# EH_400_Mini-Synth.net
KiCad netlist of a schematic drawn in EAGLE
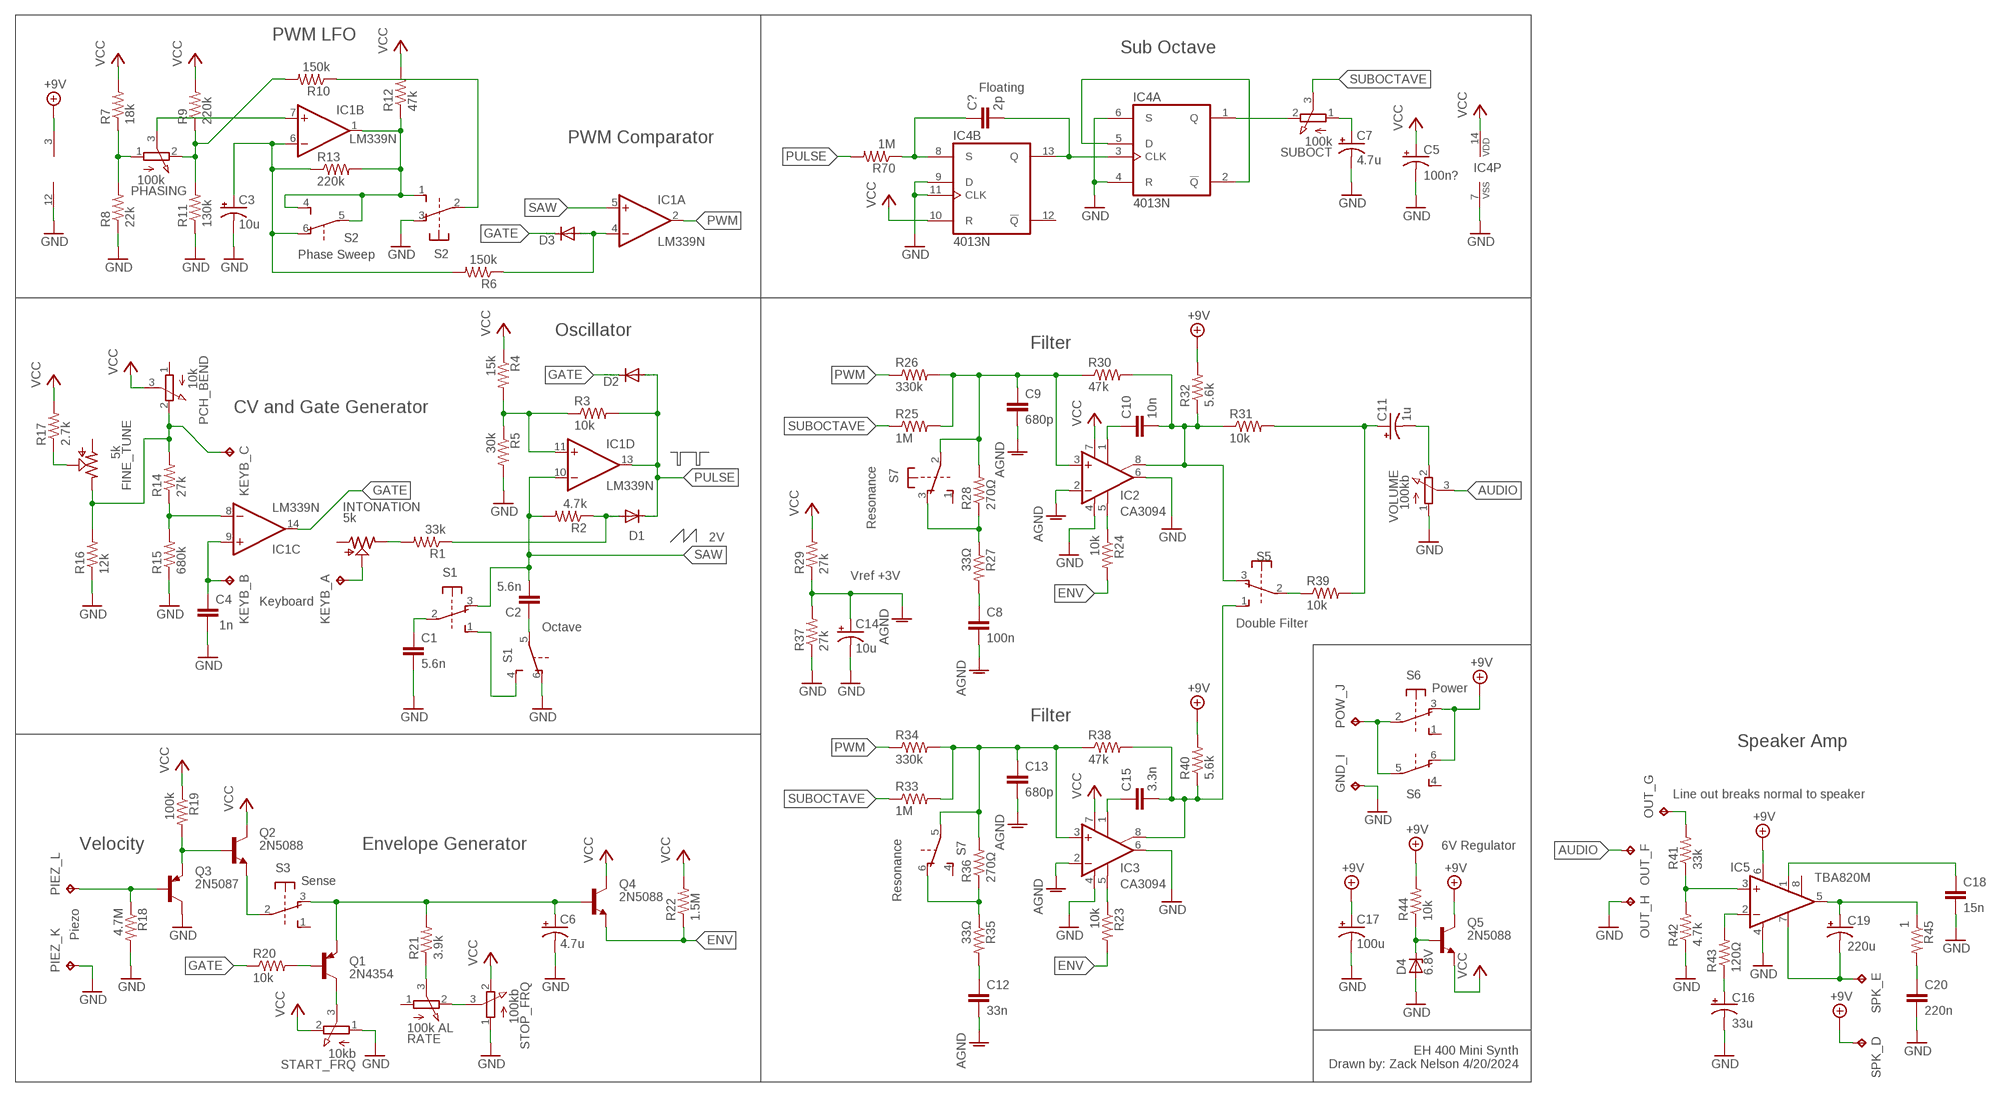
[diagram p0: schematic, sheet 1]

(export (version "E")
  (design (tool "Eeschema 10.0.6"))
  (components
    (comp (ref "C1")
      (value "5.6n")
      (footprint "eagle-import:C050-024X044")
      (libsource (lib "eagle-import") (part "C-EU050-024X044"))
    )
    (comp (ref "C2")
      (value "5.6n")
      (footprint "eagle-import:C050-024X044")
      (libsource (lib "eagle-import") (part "C-EU050-024X044"))
    )
    (comp (ref "C3")
      (value "10u")
      (footprint "eagle-import:E3,5-8")
      (libsource (lib "eagle-import") (part "CPOL-USE3.5-8"))
    )
    (comp (ref "C4")
      (value "1n")
      (footprint "eagle-import:C050-024X044")
      (libsource (lib "eagle-import") (part "C-EU050-024X044"))
    )
    (comp (ref "C5")
      (value "100n?")
      (footprint "eagle-import:E3,5-8")
      (libsource (lib "eagle-import") (part "CPOL-USE3.5-8"))
    )
    (comp (ref "C6")
      (value "4.7u")
      (footprint "eagle-import:E3,5-8")
      (libsource (lib "eagle-import") (part "CPOL-USE3.5-8"))
    )
    (comp (ref "C7")
      (value "4.7u")
      (footprint "eagle-import:E5-4")
      (libsource (lib "eagle-import") (part "CPOL-USE5-4"))
    )
    (comp (ref "C8")
      (value "100n")
      (footprint "eagle-import:C050-024X044")
      (libsource (lib "eagle-import") (part "C-EU050-024X044"))
    )
    (comp (ref "C9")
      (value "680p")
      (footprint "eagle-import:C050-024X044")
      (libsource (lib "eagle-import") (part "C-EU050-024X044"))
    )
    (comp (ref "C10")
      (value "10n")
      (footprint "eagle-import:C050-025X075")
      (libsource (lib "eagle-import") (part "C-EU050-025X075"))
    )
    (comp (ref "C11")
      (value "1u")
      (footprint "eagle-import:E5-4")
      (libsource (lib "eagle-import") (part "CPOL-USE5-4"))
    )
    (comp (ref "C12")
      (value "33n")
      (footprint "eagle-import:C050-024X044")
      (libsource (lib "eagle-import") (part "C-EU050-024X044"))
    )
    (comp (ref "C13")
      (value "680p")
      (footprint "eagle-import:C050-024X044")
      (libsource (lib "eagle-import") (part "C-EU050-024X044"))
    )
    (comp (ref "C14")
      (value "10u")
      (footprint "eagle-import:E3,5-8")
      (libsource (lib "eagle-import") (part "CPOL-USE3.5-8"))
    )
    (comp (ref "C15")
      (value "3.3n")
      (footprint "eagle-import:C050-024X044")
      (libsource (lib "eagle-import") (part "C-EU050-024X044"))
    )
    (comp (ref "C16")
      (value "33u")
      (footprint "eagle-import:E3,5-8")
      (libsource (lib "eagle-import") (part "CPOL-USE3.5-8"))
    )
    (comp (ref "C17")
      (value "100u")
      (footprint "eagle-import:TT5D9")
      (libsource (lib "eagle-import") (part "CPOL-USTT5D9"))
    )
    (comp (ref "C18")
      (value "15n")
      (footprint "eagle-import:C050-024X044")
      (libsource (lib "eagle-import") (part "C-EU050-024X044"))
    )
    (comp (ref "C19")
      (value "220u")
      (footprint "eagle-import:TT5D9")
      (libsource (lib "eagle-import") (part "CPOL-USTT5D9"))
    )
    (comp (ref "C20")
      (value "220n")
      (footprint "eagle-import:C050-024X044")
      (libsource (lib "eagle-import") (part "C-EU050-024X044"))
    )
    (comp (ref "C?")
      (value "2p")
      (footprint "eagle-import:C075-032X103")
      (libsource (lib "eagle-import") (part "C-EU075-032X103"))
    )
    (comp (ref "D1")
      (value "DIODE-DO07")
      (footprint "eagle-import:DO07")
      (libsource (lib "eagle-import") (part "DIODE-DO07"))
    )
    (comp (ref "D2")
      (value "DIODE-DO07")
      (footprint "eagle-import:DO07")
      (libsource (lib "eagle-import") (part "DIODE-DO07"))
    )
    (comp (ref "D3")
      (value "DIODE-DO07")
      (footprint "eagle-import:DO07")
      (libsource (lib "eagle-import") (part "DIODE-DO07"))
    )
    (comp (ref "D4")
      (value "6.8V")
      (footprint "eagle-import:ZDIO-7.5")
      (libsource (lib "eagle-import") (part "ZENER-DIODEZD-7.5"))
    )
    (comp (ref "FINE_TUNE")
      (value "5k")
      (footprint "eagle-import:ECP10S")
      (libsource (lib "eagle-import") (part "TRIM_US-ECP10S"))
    )
    (comp (ref "GND_I")
      (value "TPB1,27")
      (footprint "eagle-import:B1,27")
      (libsource (lib "eagle-import") (part "TPB1,27"))
    )
    (comp (ref "IC1")
      (value "LM339N")
      (footprint "eagle-import:DIL14")
      (libsource (lib "eagle-import") (part "LM339N"))
    )
    (comp (ref "IC2")
      (value "CA3094")
      (footprint "eagle-import:DIL08")
      (libsource (lib "eagle-import") (part "3080NLM"))
    )
    (comp (ref "IC3")
      (value "CA3094")
      (footprint "eagle-import:DIL08")
      (libsource (lib "eagle-import") (part "3080NLM"))
    )
    (comp (ref "IC4")
      (value "4013N")
      (footprint "eagle-import:DIL14")
      (libsource (lib "eagle-import") (part "4013N"))
    )
    (comp (ref "IC5")
      (value "TBA820M")
      (footprint "eagle-import:DIL08")
      (libsource (lib "eagle-import") (part "LM386?-N1"))
    )
    (comp (ref "INTONATION")
      (value "5k")
      (footprint "eagle-import:ECP10S")
      (libsource (lib "eagle-import") (part "TRIM_US-ECP10S"))
    )
    (comp (ref "KEYB_A")
      (value "TPB1,27")
      (footprint "eagle-import:B1,27")
      (libsource (lib "eagle-import") (part "TPB1,27"))
    )
    (comp (ref "KEYB_B")
      (value "TPB1,27")
      (footprint "eagle-import:B1,27")
      (libsource (lib "eagle-import") (part "TPB1,27"))
    )
    (comp (ref "KEYB_C")
      (value "TPB1,27")
      (footprint "eagle-import:B1,27")
      (libsource (lib "eagle-import") (part "TPB1,27"))
    )
    (comp (ref "OUT_F")
      (value "TPB1,27")
      (footprint "eagle-import:B1,27")
      (libsource (lib "eagle-import") (part "TPB1,27"))
    )
    (comp (ref "OUT_G")
      (value "TPB1,27")
      (footprint "eagle-import:B1,27")
      (libsource (lib "eagle-import") (part "TPB1,27"))
    )
    (comp (ref "OUT_H")
      (value "TPB1,27")
      (footprint "eagle-import:B1,27")
      (libsource (lib "eagle-import") (part "TPB1,27"))
    )
    (comp (ref "PCH_BEND")
      (value "10k")
      (footprint "eagle-import:FADER-EHX")
      (libsource (lib "eagle-import") (part "EVUF"))
    )
    (comp (ref "PHASING")
      (value "100k")
      (footprint "eagle-import:FADER-EHX")
      (libsource (lib "eagle-import") (part "EVUF"))
    )
    (comp (ref "PIEZ_K")
      (value "TPB1,27")
      (footprint "eagle-import:B1,27")
      (libsource (lib "eagle-import") (part "TPB1,27"))
    )
    (comp (ref "PIEZ_L")
      (value "TPB1,27")
      (footprint "eagle-import:B1,27")
      (libsource (lib "eagle-import") (part "TPB1,27"))
    )
    (comp (ref "POW_J")
      (value "TPB1,27")
      (footprint "eagle-import:B1,27")
      (libsource (lib "eagle-import") (part "TPB1,27"))
    )
    (comp (ref "Q1")
      (value "2N4354")
      (footprint "eagle-import:TO92-EBC")
      (libsource (lib "eagle-import") (part "-PNP-TO92-EBC2N5087"))
    )
    (comp (ref "Q2")
      (value "2N5088")
      (footprint "eagle-import:TO92-EBC")
      (libsource (lib "eagle-import") (part "-NPN-TO92-EBC2N5088"))
    )
    (comp (ref "Q3")
      (value "2N5087")
      (footprint "eagle-import:TO92-EBC")
      (libsource (lib "eagle-import") (part "-PNP-TO92-EBC2N5087"))
    )
    (comp (ref "Q4")
      (value "2N5088")
      (footprint "eagle-import:TO92-EBC")
      (libsource (lib "eagle-import") (part "-NPN-TO92-EBC2N5088"))
    )
    (comp (ref "Q5")
      (value "2N5088")
      (footprint "eagle-import:TO92-EBC")
      (libsource (lib "eagle-import") (part "-NPN-TO92-EBC2N5088"))
    )
    (comp (ref "R1")
      (value "33k")
      (footprint "eagle-import:0207_12")
      (libsource (lib "eagle-import") (part "R-US_0207/12"))
    )
    (comp (ref "R2")
      (value "4.7k")
      (footprint "eagle-import:0207_12")
      (libsource (lib "eagle-import") (part "R-US_0207/12"))
    )
    (comp (ref "R3")
      (value "10k")
      (footprint "eagle-import:0207_12")
      (libsource (lib "eagle-import") (part "R-US_0207/12"))
    )
    (comp (ref "R4")
      (value "15k")
      (footprint "eagle-import:0207_12")
      (libsource (lib "eagle-import") (part "R-US_0207/12"))
    )
    (comp (ref "R5")
      (value "30k")
      (footprint "eagle-import:0207_12")
      (libsource (lib "eagle-import") (part "R-US_0207/12"))
    )
    (comp (ref "R6")
      (value "150k")
      (footprint "eagle-import:0207_12")
      (libsource (lib "eagle-import") (part "R-US_0207/12"))
    )
    (comp (ref "R7")
      (value "18k")
      (footprint "eagle-import:0207_12")
      (libsource (lib "eagle-import") (part "R-US_0207/12"))
    )
    (comp (ref "R8")
      (value "22k")
      (footprint "eagle-import:0207_12")
      (libsource (lib "eagle-import") (part "R-US_0207/12"))
    )
    (comp (ref "R9")
      (value "220k")
      (footprint "eagle-import:0207_12")
      (libsource (lib "eagle-import") (part "R-US_0207/12"))
    )
    (comp (ref "R10")
      (value "150k")
      (footprint "eagle-import:0207_12")
      (libsource (lib "eagle-import") (part "R-US_0207/12"))
    )
    (comp (ref "R11")
      (value "130k")
      (footprint "eagle-import:0207_12")
      (libsource (lib "eagle-import") (part "R-US_0207/12"))
    )
    (comp (ref "R12")
      (value "47k")
      (footprint "eagle-import:0207_12")
      (libsource (lib "eagle-import") (part "R-US_0207/12"))
    )
    (comp (ref "R13")
      (value "220k")
      (footprint "eagle-import:0207_12")
      (libsource (lib "eagle-import") (part "R-US_0207/12"))
    )
    (comp (ref "R14")
      (value "27k")
      (footprint "eagle-import:0207_12")
      (libsource (lib "eagle-import") (part "R-US_0207/12"))
    )
    (comp (ref "R15")
      (value "680k")
      (footprint "eagle-import:0207_12")
      (libsource (lib "eagle-import") (part "R-US_0207/12"))
    )
    (comp (ref "R16")
      (value "12k")
      (footprint "eagle-import:0207_12")
      (libsource (lib "eagle-import") (part "R-US_0207/12"))
    )
    (comp (ref "R17")
      (value "2.7k")
      (footprint "eagle-import:0207_12")
      (libsource (lib "eagle-import") (part "R-US_0207/12"))
    )
    (comp (ref "R18")
      (value "4.7M")
      (footprint "eagle-import:0207_12")
      (libsource (lib "eagle-import") (part "R-US_0207/12"))
    )
    (comp (ref "R19")
      (value "100k")
      (footprint "eagle-import:0207_12")
      (libsource (lib "eagle-import") (part "R-US_0207/12"))
    )
    (comp (ref "R20")
      (value "10k")
      (footprint "eagle-import:0207_12")
      (libsource (lib "eagle-import") (part "R-US_0207/12"))
    )
    (comp (ref "R21")
      (value "3.9k")
      (footprint "eagle-import:0207_12")
      (libsource (lib "eagle-import") (part "R-US_0207/12"))
    )
    (comp (ref "R22")
      (value "1.5M")
      (footprint "eagle-import:0207_12")
      (libsource (lib "eagle-import") (part "R-US_0207/12"))
    )
    (comp (ref "R23")
      (value "10k")
      (footprint "eagle-import:0207_12")
      (libsource (lib "eagle-import") (part "R-US_0207/12"))
    )
    (comp (ref "R24")
      (value "10k")
      (footprint "eagle-import:0207_12")
      (libsource (lib "eagle-import") (part "R-US_0207/12"))
    )
    (comp (ref "R25")
      (value "1M")
      (footprint "eagle-import:0207_12")
      (libsource (lib "eagle-import") (part "R-US_0207/12"))
    )
    (comp (ref "R26")
      (value "330k")
      (footprint "eagle-import:0207_12")
      (libsource (lib "eagle-import") (part "R-US_0207/12"))
    )
    (comp (ref "R27")
      (value "33Ω")
      (footprint "eagle-import:0207_12")
      (libsource (lib "eagle-import") (part "R-US_0207/12"))
    )
    (comp (ref "R28")
      (value "270Ω")
      (footprint "eagle-import:0207_12")
      (libsource (lib "eagle-import") (part "R-US_0207/12"))
    )
    (comp (ref "R29")
      (value "27k")
      (footprint "eagle-import:0207_12")
      (libsource (lib "eagle-import") (part "R-US_0207/12"))
    )
    (comp (ref "R30")
      (value "47k")
      (footprint "eagle-import:0207_12")
      (libsource (lib "eagle-import") (part "R-US_0207/12"))
    )
    (comp (ref "R31")
      (value "10k")
      (footprint "eagle-import:0207_12")
      (libsource (lib "eagle-import") (part "R-US_0207/12"))
    )
    (comp (ref "R32")
      (value "5.6k")
      (footprint "eagle-import:0207_12")
      (libsource (lib "eagle-import") (part "R-US_0207/12"))
    )
    (comp (ref "R33")
      (value "1M")
      (footprint "eagle-import:0207_12")
      (libsource (lib "eagle-import") (part "R-US_0207/12"))
    )
    (comp (ref "R34")
      (value "330k")
      (footprint "eagle-import:0207_12")
      (libsource (lib "eagle-import") (part "R-US_0207/12"))
    )
    (comp (ref "R35")
      (value "33Ω")
      (footprint "eagle-import:0207_12")
      (libsource (lib "eagle-import") (part "R-US_0207/12"))
    )
    (comp (ref "R36")
      (value "270Ω")
      (footprint "eagle-import:0207_12")
      (libsource (lib "eagle-import") (part "R-US_0207/12"))
    )
    (comp (ref "R37")
      (value "27k")
      (footprint "eagle-import:0207_12")
      (libsource (lib "eagle-import") (part "R-US_0207/12"))
    )
    (comp (ref "R38")
      (value "47k")
      (footprint "eagle-import:0207_12")
      (libsource (lib "eagle-import") (part "R-US_0207/12"))
    )
    (comp (ref "R39")
      (value "10k")
      (footprint "eagle-import:0207_12")
      (libsource (lib "eagle-import") (part "R-US_0207/12"))
    )
    (comp (ref "R40")
      (value "5.6k")
      (footprint "eagle-import:0207_12")
      (libsource (lib "eagle-import") (part "R-US_0207/12"))
    )
    (comp (ref "R41")
      (value "33k")
      (footprint "eagle-import:0207_12")
      (libsource (lib "eagle-import") (part "R-US_0207/12"))
    )
    (comp (ref "R42")
      (value "4.7k")
      (footprint "eagle-import:0207_12")
      (libsource (lib "eagle-import") (part "R-US_0207/12"))
    )
    (comp (ref "R43")
      (value "120Ω")
      (footprint "eagle-import:0207_12")
      (libsource (lib "eagle-import") (part "R-US_0207/12"))
    )
    (comp (ref "R44")
      (value "10k")
      (footprint "eagle-import:0207_12")
      (libsource (lib "eagle-import") (part "R-US_0207/12"))
    )
    (comp (ref "R45")
      (value "1")
      (footprint "eagle-import:0207_12")
      (libsource (lib "eagle-import") (part "R-US_0207/12"))
    )
    (comp (ref "R70")
      (value "1M")
      (footprint "eagle-import:0207_12")
      (libsource (lib "eagle-import") (part "R-US_0207/12"))
    )
    (comp (ref "RATE")
      (value "100k AL")
      (footprint "eagle-import:FADER-EHX")
      (libsource (lib "eagle-import") (part "EVUF"))
    )
    (comp (ref "S1")
      (value "Octave")
      (footprint "eagle-import:SLIDE")
      (libsource (lib "eagle-import") (part "9077-2S"))
    )
    (comp (ref "S2")
      (value "Phase")
      (footprint "eagle-import:SLIDE")
      (libsource (lib "eagle-import") (part "9077-2S"))
    )
    (comp (ref "S3")
      (value "Sense")
      (footprint "eagle-import:SLIDE")
      (libsource (lib "eagle-import") (part "9077-2S"))
    )
    (comp (ref "S5")
      (value "Double Filter")
      (footprint "eagle-import:SLIDE")
      (libsource (lib "eagle-import") (part "9077-2S"))
    )
    (comp (ref "S6")
      (value "Power")
      (footprint "eagle-import:SLIDE")
      (libsource (lib "eagle-import") (part "9077-2S"))
    )
    (comp (ref "S7")
      (value "9077-2S")
      (footprint "eagle-import:SLIDE")
      (libsource (lib "eagle-import") (part "9077-2S"))
    )
    (comp (ref "SPK_D")
      (value "TPB1,27")
      (footprint "eagle-import:B1,27")
      (libsource (lib "eagle-import") (part "TPB1,27"))
    )
    (comp (ref "SPK_E")
      (value "TPB1,27")
      (footprint "eagle-import:B1,27")
      (libsource (lib "eagle-import") (part "TPB1,27"))
    )
    (comp (ref "START_FRQ")
      (value "10kb")
      (footprint "eagle-import:FADER-EHX")
      (libsource (lib "eagle-import") (part "EVUF"))
    )
    (comp (ref "STOP_FRQ")
      (value "100kb")
      (footprint "eagle-import:FADER-EHX")
      (libsource (lib "eagle-import") (part "EVUF"))
    )
    (comp (ref "SUBOCT")
      (value "100k")
      (footprint "eagle-import:FADER-EHX")
      (libsource (lib "eagle-import") (part "EVUF"))
    )
    (comp (ref "VOLUME")
      (value "100kb")
      (footprint "eagle-import:FADER-EHX")
      (libsource (lib "eagle-import") (part "EVUF"))
    )
  )
  (nets
    (net (code "1") (name "+9V") (class "Default")
      (node (ref "C17") (pin "+") (pinfunction "+_+") (pintype "passive"))
      (node (ref "IC1") (pin "3") (pinfunction "V+_3") (pintype "power_in"))
      (node (ref "IC5") (pin "6") (pinfunction "VS_6") (pintype "power_in"))
      (node (ref "Q5") (pin "C") (pinfunction "C_C") (pintype "passive"))
      (node (ref "R32") (pin "2") (pinfunction "2_2") (pintype "passive"))
      (node (ref "R40") (pin "2") (pinfunction "2_2") (pintype "passive"))
      (node (ref "R44") (pin "2") (pinfunction "2_2") (pintype "passive"))
      (node (ref "S6") (pin "3") (pinfunction "O_3") (pintype "passive"))
      (node (ref "S6") (pin "6") (pinfunction "O_6") (pintype "passive"))
      (node (ref "SPK_D") (pin "TP") (pinfunction "TP_TP") (pintype "input"))
    )
    (net (code "2") (name "AGND") (class "Default")
      (node (ref "C12") (pin "2") (pinfunction "2_2") (pintype "passive"))
      (node (ref "C13") (pin "2") (pinfunction "2_2") (pintype "passive"))
      (node (ref "C14") (pin "+") (pinfunction "+_+") (pintype "passive"))
      (node (ref "C8") (pin "2") (pinfunction "2_2") (pintype "passive"))
      (node (ref "C9") (pin "2") (pinfunction "2_2") (pintype "passive"))
      (node (ref "IC2") (pin "2") (pinfunction "-IN_2") (pintype "input"))
      (node (ref "IC3") (pin "2") (pinfunction "-IN_2") (pintype "input"))
      (node (ref "R29") (pin "1") (pinfunction "1_1") (pintype "passive"))
      (node (ref "R37") (pin "2") (pinfunction "2_2") (pintype "passive"))
    )
    (net (code "3") (name "AUDIO") (class "Default")
      (node (ref "OUT_F") (pin "TP") (pinfunction "TP_TP") (pintype "input"))
      (node (ref "VOLUME") (pin "3") (pinfunction "S_3") (pintype "passive"))
    )
    (net (code "4") (name "ENV") (class "Default")
      (node (ref "Q4") (pin "E") (pinfunction "E_E") (pintype "passive"))
      (node (ref "R22") (pin "1") (pinfunction "1_1") (pintype "passive"))
      (node (ref "R23") (pin "2") (pinfunction "2_2") (pintype "passive"))
      (node (ref "R24") (pin "2") (pinfunction "2_2") (pintype "passive"))
    )
    (net (code "5") (name "GATE") (class "Default")
      (node (ref "D2") (pin "C") (pinfunction "C_C") (pintype "passive"))
      (node (ref "D3") (pin "C") (pinfunction "C_C") (pintype "passive"))
      (node (ref "IC1") (pin "14") (pinfunction "OUT_14") (pintype "open_collector"))
      (node (ref "R20") (pin "1") (pinfunction "1_1") (pintype "passive"))
    )
    (net (code "6") (name "GND") (class "Default")
      (node (ref "C1") (pin "2") (pinfunction "2_2") (pintype "passive"))
      (node (ref "C14") (pin "-") (pinfunction "-_-") (pintype "passive"))
      (node (ref "C16") (pin "-") (pinfunction "-_-") (pintype "passive"))
      (node (ref "C17") (pin "-") (pinfunction "-_-") (pintype "passive"))
      (node (ref "C18") (pin "2") (pinfunction "2_2") (pintype "passive"))
      (node (ref "C20") (pin "2") (pinfunction "2_2") (pintype "passive"))
      (node (ref "C3") (pin "-") (pinfunction "-_-") (pintype "passive"))
      (node (ref "C4") (pin "2") (pinfunction "2_2") (pintype "passive"))
      (node (ref "C5") (pin "-") (pinfunction "-_-") (pintype "passive"))
      (node (ref "C6") (pin "-") (pinfunction "-_-") (pintype "passive"))
      (node (ref "C7") (pin "-") (pinfunction "-_-") (pintype "passive"))
      (node (ref "D4") (pin "A") (pinfunction "A_A") (pintype "passive"))
      (node (ref "GND_I") (pin "TP") (pinfunction "TP_TP") (pintype "input"))
      (node (ref "IC1") (pin "12") (pinfunction "GND_12") (pintype "power_in"))
      (node (ref "IC2") (pin "4") (pinfunction "V-_4") (pintype "power_in"))
      (node (ref "IC2") (pin "6") (pinfunction "OUT_6") (pintype "output"))
      (node (ref "IC3") (pin "4") (pinfunction "V-_4") (pintype "power_in"))
      (node (ref "IC3") (pin "6") (pinfunction "OUT_6") (pintype "output"))
      (node (ref "IC4") (pin "11") (pinfunction "CLK_11") (pintype "input"))
      (node (ref "IC4") (pin "4") (pinfunction "R_4") (pintype "input"))
      (node (ref "IC4") (pin "6") (pinfunction "S_6") (pintype "input"))
      (node (ref "IC4") (pin "7") (pinfunction "VSS_7") (pintype "power_in"))
      (node (ref "IC4") (pin "9") (pinfunction "D_9") (pintype "input"))
      (node (ref "IC5") (pin "4") (pinfunction "GND_4") (pintype "power_in"))
      (node (ref "OUT_H") (pin "TP") (pinfunction "TP_TP") (pintype "input"))
      (node (ref "PIEZ_K") (pin "TP") (pinfunction "TP_TP") (pintype "input"))
      (node (ref "Q3") (pin "C") (pinfunction "C_C") (pintype "passive"))
      (node (ref "R11") (pin "1") (pinfunction "1_1") (pintype "passive"))
      (node (ref "R15") (pin "1") (pinfunction "1_1") (pintype "passive"))
      (node (ref "R16") (pin "1") (pinfunction "1_1") (pintype "passive"))
      (node (ref "R18") (pin "2") (pinfunction "2_2") (pintype "passive"))
      (node (ref "R37") (pin "1") (pinfunction "1_1") (pintype "passive"))
      (node (ref "R42") (pin "1") (pinfunction "1_1") (pintype "passive"))
      (node (ref "R5") (pin "2") (pinfunction "2_2") (pintype "passive"))
      (node (ref "R8") (pin "1") (pinfunction "1_1") (pintype "passive"))
      (node (ref "S1") (pin "6") (pinfunction "O_6") (pintype "passive"))
      (node (ref "S2") (pin "3") (pinfunction "O_3") (pintype "passive"))
      (node (ref "START_FRQ") (pin "1") (pinfunction "A_1") (pintype "passive"))
      (node (ref "STOP_FRQ") (pin "1") (pinfunction "A_1") (pintype "passive"))
      (node (ref "VOLUME") (pin "1") (pinfunction "A_1") (pintype "passive"))
    )
    (net (code "7") (name "Net-(C8-Pad1)") (class "Default")
      (node (ref "C8") (pin "1") (pinfunction "1_1") (pintype "passive"))
      (node (ref "R27") (pin "2") (pinfunction "2_2") (pintype "passive"))
    )
    (net (code "8") (name "Net-(C11-Pad+)") (class "Default")
      (node (ref "C11") (pin "+") (pinfunction "+_+") (pintype "passive"))
      (node (ref "R31") (pin "2") (pinfunction "2_2") (pintype "passive"))
      (node (ref "R39") (pin "2") (pinfunction "2_2") (pintype "passive"))
    )
    (net (code "9") (name "Net-(C12-Pad1)") (class "Default")
      (node (ref "C12") (pin "1") (pinfunction "1_1") (pintype "passive"))
      (node (ref "R35") (pin "2") (pinfunction "2_2") (pintype "passive"))
    )
    (net (code "10") (name "Net-(C16-Pad+)") (class "Default")
      (node (ref "C16") (pin "+") (pinfunction "+_+") (pintype "passive"))
      (node (ref "R43") (pin "1") (pinfunction "1_1") (pintype "passive"))
    )
    (net (code "11") (name "Net-(C18-Pad1)") (class "Default")
      (node (ref "C18") (pin "1") (pinfunction "1_1") (pintype "passive"))
      (node (ref "IC5") (pin "1") (pinfunction "GAIN_1") (pintype "passive"))
    )
    (net (code "12") (name "Net-(C20-Pad1)") (class "Default")
      (node (ref "C20") (pin "1") (pinfunction "1_1") (pintype "passive"))
      (node (ref "R45") (pin "2") (pinfunction "2_2") (pintype "passive"))
    )
    (net (code "13") (name "Net-(D1-PadA)") (class "Default")
      (node (ref "D1") (pin "A") (pinfunction "A_A") (pintype "passive"))
      (node (ref "R1") (pin "1") (pinfunction "1_1") (pintype "passive"))
      (node (ref "R2") (pin "1") (pinfunction "1_1") (pintype "passive"))
    )
    (net (code "14") (name "Net-(D4-PadC)") (class "Default")
      (node (ref "D4") (pin "C") (pinfunction "C_C") (pintype "passive"))
      (node (ref "Q5") (pin "B") (pinfunction "B_B") (pintype "passive"))
      (node (ref "R44") (pin "1") (pinfunction "1_1") (pintype "passive"))
    )
    (net (code "15") (name "Net-(FINE_TUNE-PadS)") (class "Default")
      (node (ref "FINE_TUNE") (pin "S") (pinfunction "S_S") (pintype "passive"))
      (node (ref "R17") (pin "1") (pinfunction "1_1") (pintype "passive"))
    )
    (net (code "16") (name "Net-(IC1A--IN)") (class "Default")
      (node (ref "D3") (pin "A") (pinfunction "A_A") (pintype "passive"))
      (node (ref "IC1") (pin "4") (pinfunction "-IN_4") (pintype "input"))
      (node (ref "R6") (pin "1") (pinfunction "1_1") (pintype "passive"))
    )
    (net (code "17") (name "Net-(IC1B-+IN)") (class "Default")
      (node (ref "IC1") (pin "7") (pinfunction "+IN_7") (pintype "input"))
      (node (ref "PHASING") (pin "3") (pinfunction "S_3") (pintype "passive"))
    )
    (net (code "18") (name "Net-(IC1B--IN)") (class "Default")
      (node (ref "C3") (pin "+") (pinfunction "+_+") (pintype "passive"))
      (node (ref "IC1") (pin "6") (pinfunction "-IN_6") (pintype "input"))
      (node (ref "R13") (pin "1") (pinfunction "1_1") (pintype "passive"))
      (node (ref "R6") (pin "2") (pinfunction "2_2") (pintype "passive"))
      (node (ref "S2") (pin "6") (pinfunction "O_6") (pintype "passive"))
    )
    (net (code "19") (name "Net-(IC1B-OUT)") (class "Default")
      (node (ref "IC1") (pin "1") (pinfunction "OUT_1") (pintype "open_collector"))
      (node (ref "R12") (pin "1") (pinfunction "1_1") (pintype "passive"))
      (node (ref "R13") (pin "2") (pinfunction "2_2") (pintype "passive"))
      (node (ref "S2") (pin "1") (pinfunction "S_1") (pintype "passive"))
      (node (ref "S2") (pin "4") (pinfunction "S_4") (pintype "passive"))
      (node (ref "S2") (pin "5") (pinfunction "P_5") (pintype "passive"))
    )
    (net (code "20") (name "Net-(IC1C-+IN)") (class "Default")
      (node (ref "C4") (pin "1") (pinfunction "1_1") (pintype "passive"))
      (node (ref "IC1") (pin "9") (pinfunction "+IN_9") (pintype "input"))
      (node (ref "KEYB_B") (pin "TP") (pinfunction "TP_TP") (pintype "input"))
    )
    (net (code "21") (name "Net-(IC1C--IN)") (class "Default")
      (node (ref "IC1") (pin "8") (pinfunction "-IN_8") (pintype "input"))
      (node (ref "R14") (pin "1") (pinfunction "1_1") (pintype "passive"))
      (node (ref "R15") (pin "2") (pinfunction "2_2") (pintype "passive"))
    )
    (net (code "22") (name "Net-(IC1D-+IN)") (class "Default")
      (node (ref "IC1") (pin "11") (pinfunction "+IN_11") (pintype "input"))
      (node (ref "R3") (pin "1") (pinfunction "1_1") (pintype "passive"))
      (node (ref "R4") (pin "2") (pinfunction "2_2") (pintype "passive"))
      (node (ref "R5") (pin "1") (pinfunction "1_1") (pintype "passive"))
    )
    (net (code "23") (name "Net-(IC2-+IN)") (class "Default")
      (node (ref "C9") (pin "1") (pinfunction "1_1") (pintype "passive"))
      (node (ref "IC2") (pin "3") (pinfunction "+IN_3") (pintype "input"))
      (node (ref "R25") (pin "2") (pinfunction "2_2") (pintype "passive"))
      (node (ref "R26") (pin "2") (pinfunction "2_2") (pintype "passive"))
      (node (ref "R28") (pin "2") (pinfunction "2_2") (pintype "passive"))
      (node (ref "R30") (pin "1") (pinfunction "1_1") (pintype "passive"))
      (node (ref "S7") (pin "2") (pinfunction "P_2") (pintype "passive"))
    )
    (net (code "24") (name "Net-(IC2-ON1)") (class "Default")
      (node (ref "C10") (pin "1") (pinfunction "1_1") (pintype "passive"))
      (node (ref "IC2") (pin "1") (pinfunction "ON1_1") (pintype "passive"))
    )
    (net (code "25") (name "Net-(IC2-ON2)") (class "Default")
      (node (ref "C10") (pin "2") (pinfunction "2_2") (pintype "passive"))
      (node (ref "IC2") (pin "8") (pinfunction "ON2_8") (pintype "passive"))
      (node (ref "R30") (pin "2") (pinfunction "2_2") (pintype "passive"))
      (node (ref "R31") (pin "1") (pinfunction "1_1") (pintype "passive"))
      (node (ref "R32") (pin "1") (pinfunction "1_1") (pintype "passive"))
      (node (ref "S5") (pin "3") (pinfunction "O_3") (pintype "passive"))
    )
    (net (code "26") (name "Net-(IC2-OPT)") (class "Default")
      (node (ref "IC2") (pin "5") (pinfunction "OPT_5") (pintype "passive"))
      (node (ref "R24") (pin "1") (pinfunction "1_1") (pintype "passive"))
    )
    (net (code "27") (name "Net-(IC3-+IN)") (class "Default")
      (node (ref "C13") (pin "1") (pinfunction "1_1") (pintype "passive"))
      (node (ref "IC3") (pin "3") (pinfunction "+IN_3") (pintype "input"))
      (node (ref "R33") (pin "2") (pinfunction "2_2") (pintype "passive"))
      (node (ref "R34") (pin "2") (pinfunction "2_2") (pintype "passive"))
      (node (ref "R36") (pin "2") (pinfunction "2_2") (pintype "passive"))
      (node (ref "R38") (pin "1") (pinfunction "1_1") (pintype "passive"))
      (node (ref "S7") (pin "5") (pinfunction "P_5") (pintype "passive"))
    )
    (net (code "28") (name "Net-(IC3-ON1)") (class "Default")
      (node (ref "C15") (pin "1") (pinfunction "1_1") (pintype "passive"))
      (node (ref "IC3") (pin "1") (pinfunction "ON1_1") (pintype "passive"))
    )
    (net (code "29") (name "Net-(IC3-ON2)") (class "Default")
      (node (ref "C15") (pin "2") (pinfunction "2_2") (pintype "passive"))
      (node (ref "IC3") (pin "8") (pinfunction "ON2_8") (pintype "passive"))
      (node (ref "R38") (pin "2") (pinfunction "2_2") (pintype "passive"))
      (node (ref "R40") (pin "1") (pinfunction "1_1") (pintype "passive"))
      (node (ref "S5") (pin "1") (pinfunction "S_1") (pintype "passive"))
    )
    (net (code "30") (name "Net-(IC3-OPT)") (class "Default")
      (node (ref "IC3") (pin "5") (pinfunction "OPT_5") (pintype "passive"))
      (node (ref "R23") (pin "1") (pinfunction "1_1") (pintype "passive"))
    )
    (net (code "31") (name "Net-(IC4A-CLK)") (class "Default")
      (node (ref "C?") (pin "2") (pinfunction "2_2") (pintype "passive"))
      (node (ref "IC4") (pin "13") (pinfunction "Q_13") (pintype "output"))
      (node (ref "IC4") (pin "3") (pinfunction "CLK_3") (pintype "input"))
    )
    (net (code "32") (name "Net-(IC4A-D)") (class "Default")
      (node (ref "IC4") (pin "2") (pinfunction "~{Q}_2") (pintype "output"))
      (node (ref "IC4") (pin "5") (pinfunction "D_5") (pintype "input"))
    )
    (net (code "33") (name "Net-(IC4A-Q)") (class "Default")
      (node (ref "IC4") (pin "1") (pinfunction "Q_1") (pintype "output"))
      (node (ref "SUBOCT") (pin "2") (pinfunction "E_2") (pintype "passive"))
    )
    (net (code "34") (name "Net-(IC4B-S)") (class "Default")
      (node (ref "C?") (pin "1") (pinfunction "1_1") (pintype "passive"))
      (node (ref "IC4") (pin "8") (pinfunction "S_8") (pintype "input"))
      (node (ref "R70") (pin "1") (pinfunction "1_1") (pintype "passive"))
    )
    (net (code "35") (name "Net-(IC5-+IN)") (class "Default")
      (node (ref "IC5") (pin "3") (pinfunction "+IN_3") (pintype "input"))
      (node (ref "R41") (pin "1") (pinfunction "1_1") (pintype "passive"))
      (node (ref "R42") (pin "2") (pinfunction "2_2") (pintype "passive"))
    )
    (net (code "36") (name "Net-(IC5--IN)") (class "Default")
      (node (ref "IC5") (pin "2") (pinfunction "-IN_2") (pintype "input"))
      (node (ref "R43") (pin "2") (pinfunction "2_2") (pintype "passive"))
    )
    (net (code "37") (name "Net-(IC5-BYPASS)") (class "Default")
      (node (ref "C19") (pin "-") (pinfunction "-_-") (pintype "passive"))
      (node (ref "IC5") (pin "7") (pinfunction "BYPASS_7") (pintype "passive"))
      (node (ref "SPK_E") (pin "TP") (pinfunction "TP_TP") (pintype "input"))
    )
    (net (code "38") (name "Net-(IC5-OUT)") (class "Default")
      (node (ref "C19") (pin "+") (pinfunction "+_+") (pintype "passive"))
      (node (ref "IC5") (pin "5") (pinfunction "OUT_5") (pintype "output"))
      (node (ref "R45") (pin "1") (pinfunction "1_1") (pintype "passive"))
    )
    (net (code "39") (name "Net-(INTONATION-PadE)") (class "Default")
      (node (ref "INTONATION") (pin "E") (pinfunction "E_E") (pintype "passive"))
      (node (ref "R1") (pin "2") (pinfunction "2_2") (pintype "passive"))
    )
    (net (code "40") (name "Net-(INTONATION-PadS)") (class "Default")
      (node (ref "INTONATION") (pin "S") (pinfunction "S_S") (pintype "passive"))
      (node (ref "KEYB_A") (pin "TP") (pinfunction "TP_TP") (pintype "input"))
    )
    (net (code "41") (name "Net-(OUT_G-PadTP)") (class "Default")
      (node (ref "OUT_G") (pin "TP") (pinfunction "TP_TP") (pintype "input"))
      (node (ref "R41") (pin "2") (pinfunction "2_2") (pintype "passive"))
    )
    (net (code "42") (name "Net-(PCH_BEND-E)") (class "Default")
      (node (ref "FINE_TUNE") (pin "E") (pinfunction "E_E") (pintype "passive"))
      (node (ref "KEYB_C") (pin "TP") (pinfunction "TP_TP") (pintype "input"))
      (node (ref "PCH_BEND") (pin "2") (pinfunction "E_2") (pintype "passive"))
      (node (ref "R14") (pin "2") (pinfunction "2_2") (pintype "passive"))
      (node (ref "R16") (pin "2") (pinfunction "2_2") (pintype "passive"))
    )
    (net (code "43") (name "Net-(PHASING-A)") (class "Default")
      (node (ref "PHASING") (pin "1") (pinfunction "A_1") (pintype "passive"))
      (node (ref "R7") (pin "1") (pinfunction "1_1") (pintype "passive"))
      (node (ref "R8") (pin "2") (pinfunction "2_2") (pintype "passive"))
    )
    (net (code "44") (name "Net-(PHASING-E)") (class "Default")
      (node (ref "PHASING") (pin "2") (pinfunction "E_2") (pintype "passive"))
      (node (ref "R10") (pin "2") (pinfunction "2_2") (pintype "passive"))
      (node (ref "R11") (pin "2") (pinfunction "2_2") (pintype "passive"))
      (node (ref "R9") (pin "1") (pinfunction "1_1") (pintype "passive"))
    )
    (net (code "45") (name "Net-(PIEZ_L-PadTP)") (class "Default")
      (node (ref "PIEZ_L") (pin "TP") (pinfunction "TP_TP") (pintype "input"))
      (node (ref "Q3") (pin "B") (pinfunction "B_B") (pintype "passive"))
      (node (ref "R18") (pin "1") (pinfunction "1_1") (pintype "passive"))
    )
    (net (code "46") (name "Net-(Q1-PadB)") (class "Default")
      (node (ref "Q1") (pin "B") (pinfunction "B_B") (pintype "passive"))
      (node (ref "R20") (pin "2") (pinfunction "2_2") (pintype "passive"))
    )
    (net (code "47") (name "Net-(Q2-PadB)") (class "Default")
      (node (ref "Q2") (pin "B") (pinfunction "B_B") (pintype "passive"))
      (node (ref "Q3") (pin "E") (pinfunction "E_E") (pintype "passive"))
      (node (ref "R19") (pin "2") (pinfunction "2_2") (pintype "passive"))
    )
    (net (code "48") (name "Net-(RATE-E)") (class "Default")
      (node (ref "RATE") (pin "2") (pinfunction "E_2") (pintype "passive"))
      (node (ref "STOP_FRQ") (pin "3") (pinfunction "S_3") (pintype "passive"))
    )
    (net (code "49") (name "Net-(RATE-S)") (class "Default")
      (node (ref "R21") (pin "1") (pinfunction "1_1") (pintype "passive"))
      (node (ref "RATE") (pin "3") (pinfunction "S_3") (pintype "passive"))
    )
    (net (code "50") (name "Net-(S1A-P)") (class "Default")
      (node (ref "C1") (pin "1") (pinfunction "1_1") (pintype "passive"))
      (node (ref "S1") (pin "2") (pinfunction "P_2") (pintype "passive"))
    )
    (net (code "51") (name "Net-(S1A-S)") (class "Default")
      (node (ref "S1") (pin "1") (pinfunction "S_1") (pintype "passive"))
      (node (ref "S1") (pin "4") (pinfunction "S_4") (pintype "passive"))
    )
    (net (code "52") (name "Net-(S1B-P)") (class "Default")
      (node (ref "C2") (pin "1") (pinfunction "1_1") (pintype "passive"))
      (node (ref "S1") (pin "5") (pinfunction "P_5") (pintype "passive"))
    )
    (net (code "53") (name "Net-(S2A-P)") (class "Default")
      (node (ref "R10") (pin "1") (pinfunction "1_1") (pintype "passive"))
      (node (ref "S2") (pin "2") (pinfunction "P_2") (pintype "passive"))
    )
    (net (code "54") (name "Net-(S3A-O)") (class "Default")
      (node (ref "C6") (pin "+") (pinfunction "+_+") (pintype "passive"))
      (node (ref "Q1") (pin "E") (pinfunction "E_E") (pintype "passive"))
      (node (ref "Q4") (pin "B") (pinfunction "B_B") (pintype "passive"))
      (node (ref "R21") (pin "2") (pinfunction "2_2") (pintype "passive"))
      (node (ref "S3") (pin "3") (pinfunction "O_3") (pintype "passive"))
    )
    (net (code "55") (name "Net-(S3A-P)") (class "Default")
      (node (ref "Q2") (pin "E") (pinfunction "E_E") (pintype "passive"))
      (node (ref "S3") (pin "2") (pinfunction "P_2") (pintype "passive"))
    )
    (net (code "56") (name "Net-(S5A-P)") (class "Default")
      (node (ref "R39") (pin "1") (pinfunction "1_1") (pintype "passive"))
      (node (ref "S5") (pin "2") (pinfunction "P_2") (pintype "passive"))
    )
    (net (code "57") (name "Net-(S6A-P)") (class "Default")
      (node (ref "POW_J") (pin "TP") (pinfunction "TP_TP") (pintype "input"))
      (node (ref "S6") (pin "2") (pinfunction "P_2") (pintype "passive"))
      (node (ref "S6") (pin "5") (pinfunction "P_5") (pintype "passive"))
    )
    (net (code "58") (name "Net-(S7A-O)") (class "Default")
      (node (ref "R27") (pin "1") (pinfunction "1_1") (pintype "passive"))
      (node (ref "R28") (pin "1") (pinfunction "1_1") (pintype "passive"))
      (node (ref "S7") (pin "3") (pinfunction "O_3") (pintype "passive"))
    )
    (net (code "59") (name "Net-(S7B-O)") (class "Default")
      (node (ref "R35") (pin "1") (pinfunction "1_1") (pintype "passive"))
      (node (ref "R36") (pin "1") (pinfunction "1_1") (pintype "passive"))
      (node (ref "S7") (pin "6") (pinfunction "O_6") (pintype "passive"))
    )
    (net (code "60") (name "Net-(START_FRQ-S)") (class "Default")
      (node (ref "Q1") (pin "C") (pinfunction "C_C") (pintype "passive"))
      (node (ref "START_FRQ") (pin "3") (pinfunction "S_3") (pintype "passive"))
    )
    (net (code "61") (name "Net-(SUBOCT-A)") (class "Default")
      (node (ref "C7") (pin "+") (pinfunction "+_+") (pintype "passive"))
      (node (ref "SUBOCT") (pin "1") (pinfunction "A_1") (pintype "passive"))
    )
    (net (code "62") (name "Net-(VOLUME-E)") (class "Default")
      (node (ref "C11") (pin "-") (pinfunction "-_-") (pintype "passive"))
      (node (ref "VOLUME") (pin "2") (pinfunction "E_2") (pintype "passive"))
    )
    (net (code "63") (name "PULSE") (class "Default")
      (node (ref "D1") (pin "C") (pinfunction "C_C") (pintype "passive"))
      (node (ref "D2") (pin "A") (pinfunction "A_A") (pintype "passive"))
      (node (ref "IC1") (pin "13") (pinfunction "OUT_13") (pintype "open_collector"))
      (node (ref "R3") (pin "2") (pinfunction "2_2") (pintype "passive"))
      (node (ref "R70") (pin "2") (pinfunction "2_2") (pintype "passive"))
    )
    (net (code "64") (name "PWM") (class "Default")
      (node (ref "IC1") (pin "2") (pinfunction "OUT_2") (pintype "open_collector"))
      (node (ref "R26") (pin "1") (pinfunction "1_1") (pintype "passive"))
      (node (ref "R34") (pin "1") (pinfunction "1_1") (pintype "passive"))
    )
    (net (code "65") (name "SAW") (class "Default")
      (node (ref "C2") (pin "2") (pinfunction "2_2") (pintype "passive"))
      (node (ref "IC1") (pin "10") (pinfunction "-IN_10") (pintype "input"))
      (node (ref "IC1") (pin "5") (pinfunction "+IN_5") (pintype "input"))
      (node (ref "R2") (pin "2") (pinfunction "2_2") (pintype "passive"))
      (node (ref "S1") (pin "3") (pinfunction "O_3") (pintype "passive"))
    )
    (net (code "66") (name "SUBOCTAVE") (class "Default")
      (node (ref "R25") (pin "1") (pinfunction "1_1") (pintype "passive"))
      (node (ref "R33") (pin "1") (pinfunction "1_1") (pintype "passive"))
      (node (ref "SUBOCT") (pin "3") (pinfunction "S_3") (pintype "passive"))
    )
    (net (code "67") (name "VCC") (class "Default")
      (node (ref "C5") (pin "+") (pinfunction "+_+") (pintype "passive"))
      (node (ref "IC2") (pin "7") (pinfunction "V+_7") (pintype "power_in"))
      (node (ref "IC3") (pin "7") (pinfunction "V+_7") (pintype "power_in"))
      (node (ref "IC4") (pin "10") (pinfunction "R_10") (pintype "input"))
      (node (ref "IC4") (pin "14") (pinfunction "VDD_14") (pintype "power_in"))
      (node (ref "PCH_BEND") (pin "3") (pinfunction "S_3") (pintype "passive"))
      (node (ref "Q2") (pin "C") (pinfunction "C_C") (pintype "passive"))
      (node (ref "Q4") (pin "C") (pinfunction "C_C") (pintype "passive"))
      (node (ref "Q5") (pin "E") (pinfunction "E_E") (pintype "passive"))
      (node (ref "R12") (pin "2") (pinfunction "2_2") (pintype "passive"))
      (node (ref "R17") (pin "2") (pinfunction "2_2") (pintype "passive"))
      (node (ref "R19") (pin "1") (pinfunction "1_1") (pintype "passive"))
      (node (ref "R22") (pin "2") (pinfunction "2_2") (pintype "passive"))
      (node (ref "R29") (pin "2") (pinfunction "2_2") (pintype "passive"))
      (node (ref "R4") (pin "1") (pinfunction "1_1") (pintype "passive"))
      (node (ref "R7") (pin "2") (pinfunction "2_2") (pintype "passive"))
      (node (ref "R9") (pin "2") (pinfunction "2_2") (pintype "passive"))
      (node (ref "START_FRQ") (pin "2") (pinfunction "E_2") (pintype "passive"))
      (node (ref "STOP_FRQ") (pin "2") (pinfunction "E_2") (pintype "passive"))
    )
    (net (code "68") (name "unconnected-(FINE_TUNE-PadA)") (class "Default")
      (node (ref "FINE_TUNE") (pin "A") (pinfunction "A_A") (pintype "passive"))
    )
    (net (code "69") (name "unconnected-(IC4B-~{Q}-Pad12)") (class "Default")
      (node (ref "IC4") (pin "12") (pinfunction "~{Q}_12") (pintype "output"))
    )
    (net (code "70") (name "unconnected-(IC5-GAIN-Pad8)") (class "Default")
      (node (ref "IC5") (pin "8") (pinfunction "GAIN_8") (pintype "passive"))
    )
    (net (code "71") (name "unconnected-(INTONATION-PadA)") (class "Default")
      (node (ref "INTONATION") (pin "A") (pinfunction "A_A") (pintype "passive"))
    )
    (net (code "72") (name "unconnected-(PCH_BEND-A-Pad1)") (class "Default")
      (node (ref "PCH_BEND") (pin "1") (pinfunction "A_1") (pintype "passive"))
    )
    (net (code "73") (name "unconnected-(RATE-A-Pad1)") (class "Default")
      (node (ref "RATE") (pin "1") (pinfunction "A_1") (pintype "passive"))
    )
    (net (code "74") (name "unconnected-(S3A-S-Pad1)") (class "Default")
      (node (ref "S3") (pin "1") (pinfunction "S_1") (pintype "passive"))
    )
    (net (code "75") (name "unconnected-(S6A-S-Pad1)") (class "Default")
      (node (ref "S6") (pin "1") (pinfunction "S_1") (pintype "passive"))
    )
    (net (code "76") (name "unconnected-(S6B-S-Pad4)") (class "Default")
      (node (ref "S6") (pin "4") (pinfunction "S_4") (pintype "passive"))
    )
    (net (code "77") (name "unconnected-(S7A-S-Pad1)") (class "Default")
      (node (ref "S7") (pin "1") (pinfunction "S_1") (pintype "passive"))
    )
    (net (code "78") (name "unconnected-(S7B-S-Pad4)") (class "Default")
      (node (ref "S7") (pin "4") (pinfunction "S_4") (pintype "passive"))
    )
  )
)
